# ESC.net
KiCad netlist of a schematic drawn in EAGLE
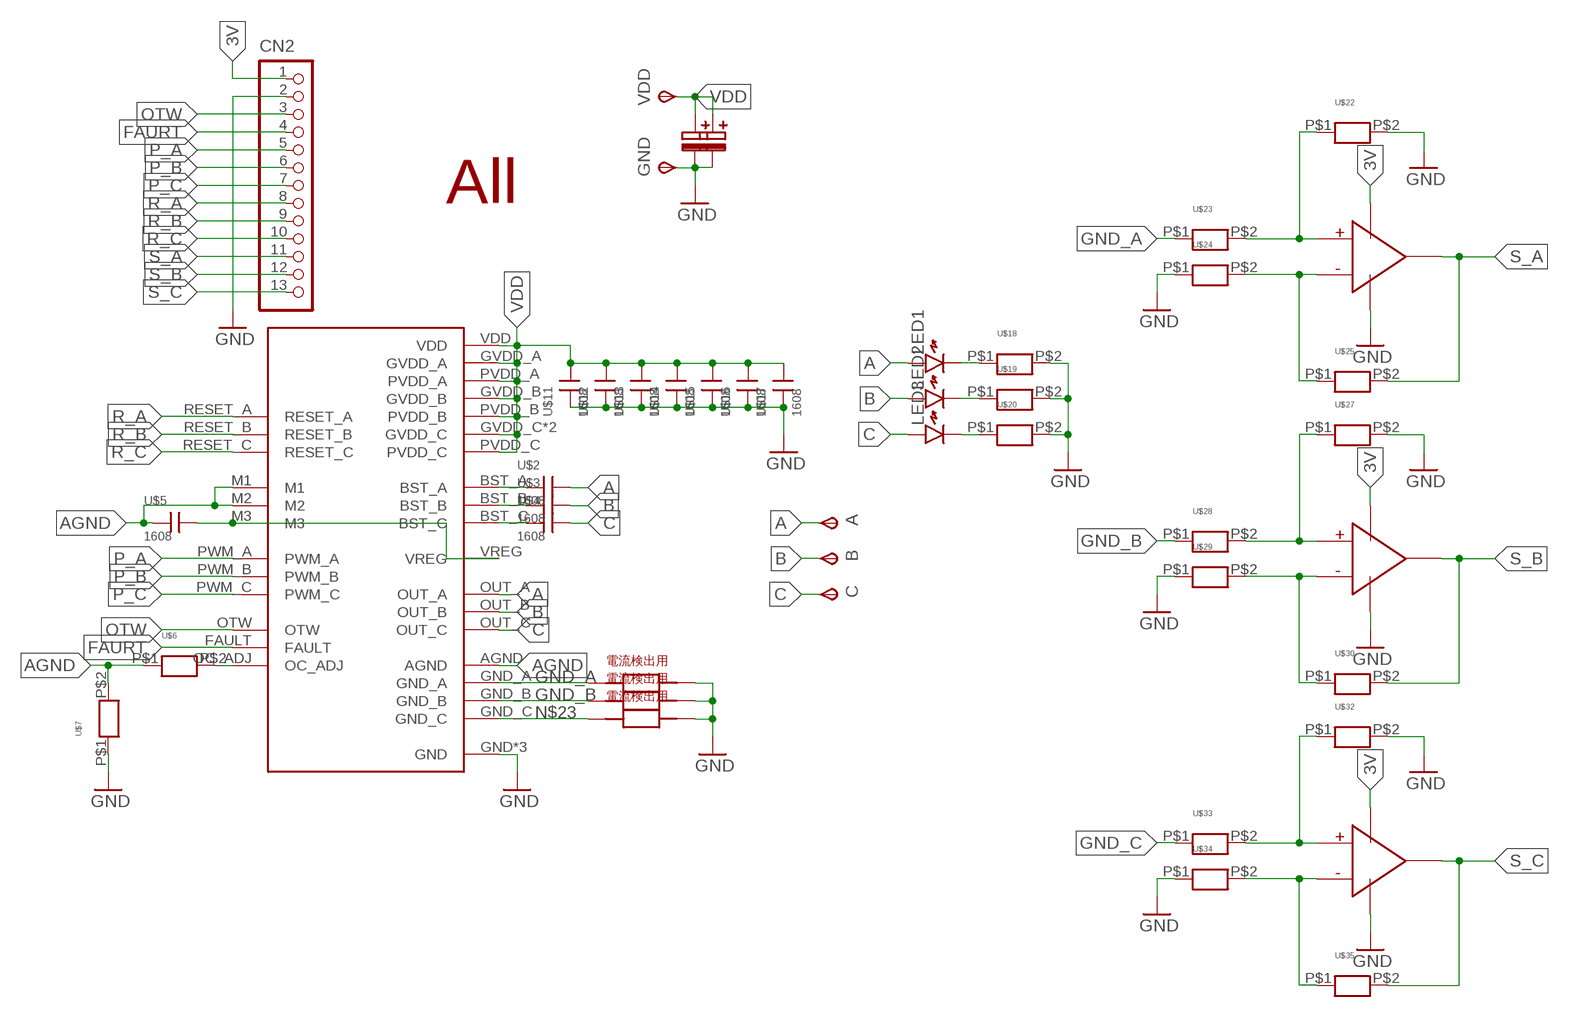
[diagram p0: schematic, sheet 1]

(export (version "E")
  (design (tool "Eeschema 10.0.6"))
  (components
    (comp (ref "A")
      (value "TPSPAD1-20")
      (footprint "eagle-import:P1-20")
      (libsource (lib "eagle-import") (part "TPSPAD1-20"))
    )
    (comp (ref "B")
      (value "TPSPAD1-20")
      (footprint "eagle-import:P1-20")
      (libsource (lib "eagle-import") (part "TPSPAD1-20"))
    )
    (comp (ref "C")
      (value "TPSPAD1-20")
      (footprint "eagle-import:P1-20")
      (libsource (lib "eagle-import") (part "TPSPAD1-20"))
    )
    (comp (ref "CN2")
      (value "B13B-XH-A")
      (footprint "eagle-import:B13B-XH-A")
      (libsource (lib "eagle-import") (part "B13B-XH-A"))
    )
    (comp (ref "GND")
      (value "TPSPAD1-20")
      (footprint "eagle-import:P1-20")
      (libsource (lib "eagle-import") (part "TPSPAD1-20"))
    )
    (comp (ref "LED1")
      (value "LED1608")
      (footprint "eagle-import:LED1608")
      (libsource (lib "eagle-import") (part "LED1608"))
    )
    (comp (ref "LED2")
      (value "LED1608")
      (footprint "eagle-import:LED1608")
      (libsource (lib "eagle-import") (part "LED1608"))
    )
    (comp (ref "LED3")
      (value "LED1608")
      (footprint "eagle-import:LED1608")
      (libsource (lib "eagle-import") (part "LED1608"))
    )
    (comp (ref "U$1")
      (value "DRV8332")
      (footprint "eagle-import:DRV8332")
      (libsource (lib "eagle-import") (part "DRV8332"))
    )
    (comp (ref "U$2")
      (value "1608")
      (footprint "eagle-import:CON")
      (libsource (lib "eagle-import") (part "1608"))
    )
    (comp (ref "U$3")
      (value "1608")
      (footprint "eagle-import:CON")
      (libsource (lib "eagle-import") (part "1608"))
    )
    (comp (ref "U$4")
      (value "1608")
      (footprint "eagle-import:CON")
      (libsource (lib "eagle-import") (part "1608"))
    )
    (comp (ref "U$5")
      (value "1608")
      (footprint "eagle-import:CON")
      (libsource (lib "eagle-import") (part "1608"))
    )
    (comp (ref "U$6") (value "R") (footprint "eagle-import:1608") (libsource (lib "eagle-import") (part "R")))
    (comp (ref "U$7") (value "R") (footprint "eagle-import:1608") (libsource (lib "eagle-import") (part "R")))
    (comp (ref "U$8")
      (value "R0.1")
      (footprint "eagle-import:R0.1")
      (libsource (lib "eagle-import") (part "R0.1"))
    )
    (comp (ref "U$9")
      (value "R0.1")
      (footprint "eagle-import:R0.1")
      (libsource (lib "eagle-import") (part "R0.1"))
    )
    (comp (ref "U$10")
      (value "R0.1")
      (footprint "eagle-import:R0.1")
      (libsource (lib "eagle-import") (part "R0.1"))
    )
    (comp (ref "U$11")
      (value "1608")
      (footprint "eagle-import:CON")
      (libsource (lib "eagle-import") (part "1608"))
    )
    (comp (ref "U$12")
      (value "1608")
      (footprint "eagle-import:CON")
      (libsource (lib "eagle-import") (part "1608"))
    )
    (comp (ref "U$13")
      (value "1608")
      (footprint "eagle-import:CON")
      (libsource (lib "eagle-import") (part "1608"))
    )
    (comp (ref "U$14")
      (value "1608")
      (footprint "eagle-import:CON")
      (libsource (lib "eagle-import") (part "1608"))
    )
    (comp (ref "U$15")
      (value "1608")
      (footprint "eagle-import:CON")
      (libsource (lib "eagle-import") (part "1608"))
    )
    (comp (ref "U$16")
      (value "1608")
      (footprint "eagle-import:CON")
      (libsource (lib "eagle-import") (part "1608"))
    )
    (comp (ref "U$17")
      (value "1608")
      (footprint "eagle-import:CON")
      (libsource (lib "eagle-import") (part "1608"))
    )
    (comp (ref "U$18")
      (value "R")
      (footprint "eagle-import:1608")
      (libsource (lib "eagle-import") (part "R"))
    )
    (comp (ref "U$19")
      (value "R")
      (footprint "eagle-import:1608")
      (libsource (lib "eagle-import") (part "R"))
    )
    (comp (ref "U$20")
      (value "R")
      (footprint "eagle-import:1608")
      (libsource (lib "eagle-import") (part "R"))
    )
    (comp (ref "U$21")
      (value "77701")
      (footprint "eagle-import:77701")
      (libsource (lib "eagle-import") (part "77701"))
    )
    (comp (ref "U$22")
      (value "R")
      (footprint "eagle-import:1608")
      (libsource (lib "eagle-import") (part "R"))
    )
    (comp (ref "U$23")
      (value "R")
      (footprint "eagle-import:1608")
      (libsource (lib "eagle-import") (part "R"))
    )
    (comp (ref "U$24")
      (value "R")
      (footprint "eagle-import:1608")
      (libsource (lib "eagle-import") (part "R"))
    )
    (comp (ref "U$25")
      (value "R")
      (footprint "eagle-import:1608")
      (libsource (lib "eagle-import") (part "R"))
    )
    (comp (ref "U$26")
      (value "77701")
      (footprint "eagle-import:77701")
      (libsource (lib "eagle-import") (part "77701"))
    )
    (comp (ref "U$27")
      (value "R")
      (footprint "eagle-import:1608")
      (libsource (lib "eagle-import") (part "R"))
    )
    (comp (ref "U$28")
      (value "R")
      (footprint "eagle-import:1608")
      (libsource (lib "eagle-import") (part "R"))
    )
    (comp (ref "U$29")
      (value "R")
      (footprint "eagle-import:1608")
      (libsource (lib "eagle-import") (part "R"))
    )
    (comp (ref "U$30")
      (value "R")
      (footprint "eagle-import:1608")
      (libsource (lib "eagle-import") (part "R"))
    )
    (comp (ref "U$31")
      (value "77701")
      (footprint "eagle-import:77701")
      (libsource (lib "eagle-import") (part "77701"))
    )
    (comp (ref "U$32")
      (value "R")
      (footprint "eagle-import:1608")
      (libsource (lib "eagle-import") (part "R"))
    )
    (comp (ref "U$33")
      (value "R")
      (footprint "eagle-import:1608")
      (libsource (lib "eagle-import") (part "R"))
    )
    (comp (ref "U$34")
      (value "R")
      (footprint "eagle-import:1608")
      (libsource (lib "eagle-import") (part "R"))
    )
    (comp (ref "U$35")
      (value "R")
      (footprint "eagle-import:1608")
      (libsource (lib "eagle-import") (part "R"))
    )
    (comp (ref "U$36")
      (value "25V100")
      (footprint "eagle-import:25V100")
      (libsource (lib "eagle-import") (part "25V100"))
    )
    (comp (ref "U$37")
      (value "25V100")
      (footprint "eagle-import:25V100")
      (libsource (lib "eagle-import") (part "25V100"))
    )
    (comp (ref "U$38")
      (value "ALL")
      (footprint "eagle-import:ALL")
      (libsource (lib "eagle-import") (part "ALL"))
    )
    (comp (ref "VDD")
      (value "TPSPAD1-20")
      (footprint "eagle-import:P1-20")
      (libsource (lib "eagle-import") (part "TPSPAD1-20"))
    )
  )
  (nets
    (net (code "1") (name "/N$23") (class "Default")
      (node (ref "U$1") (pin "GND_C") (pinfunction "GND_C_GND_C") (pintype "bidirectional"))
      (node (ref "U$10") (pin "P$1") (pinfunction "P$1_P$1") (pintype "bidirectional"))
    )
    (net (code "2") (name "3V") (class "Default")
      (node (ref "CN2") (pin "1") (pinfunction "1_1") (pintype "passive"))
      (node (ref "U$21") (pin "VIN") (pinfunction "VIN_VIN") (pintype "bidirectional"))
      (node (ref "U$26") (pin "VIN") (pinfunction "VIN_VIN") (pintype "bidirectional"))
      (node (ref "U$31") (pin "VIN") (pinfunction "VIN_VIN") (pintype "bidirectional"))
    )
    (net (code "3") (name "A") (class "Default")
      (node (ref "A") (pin "TP") (pinfunction "PP_TP") (pintype "input"))
      (node (ref "LED1") (pin "A") (pinfunction "A_A") (pintype "passive"))
      (node (ref "U$1") (pin "OUT_A") (pinfunction "OUT_A_OUT_A") (pintype "bidirectional"))
      (node (ref "U$2") (pin "P$1") (pinfunction "1_P$1") (pintype "bidirectional"))
    )
    (net (code "4") (name "AGND") (class "Default")
      (node (ref "U$1") (pin "AGND") (pinfunction "AGND_AGND") (pintype "bidirectional"))
      (node (ref "U$1") (pin "M1") (pinfunction "M1_M1") (pintype "bidirectional"))
      (node (ref "U$1") (pin "M2") (pinfunction "M2_M2") (pintype "bidirectional"))
      (node (ref "U$5") (pin "P$2") (pinfunction "2_P$2") (pintype "bidirectional"))
      (node (ref "U$6") (pin "P$1") (pinfunction "P$1_P$1") (pintype "bidirectional"))
      (node (ref "U$7") (pin "P$2") (pinfunction "P$2_P$2") (pintype "bidirectional"))
    )
    (net (code "5") (name "B") (class "Default")
      (node (ref "B") (pin "TP") (pinfunction "PP_TP") (pintype "input"))
      (node (ref "LED2") (pin "A") (pinfunction "A_A") (pintype "passive"))
      (node (ref "U$1") (pin "OUT_B") (pinfunction "OUT_B_OUT_B") (pintype "bidirectional"))
      (node (ref "U$3") (pin "P$1") (pinfunction "1_P$1") (pintype "bidirectional"))
    )
    (net (code "6") (name "C") (class "Default")
      (node (ref "C") (pin "TP") (pinfunction "PP_TP") (pintype "input"))
      (node (ref "LED3") (pin "A") (pinfunction "A_A") (pintype "passive"))
      (node (ref "U$1") (pin "OUT_C") (pinfunction "OUT_C_OUT_C") (pintype "bidirectional"))
      (node (ref "U$4") (pin "P$1") (pinfunction "1_P$1") (pintype "bidirectional"))
    )
    (net (code "7") (name "FAURT") (class "Default")
      (node (ref "CN2") (pin "4") (pinfunction "4_4") (pintype "passive"))
      (node (ref "U$1") (pin "FAULT") (pinfunction "FAULT_FAULT") (pintype "bidirectional"))
    )
    (net (code "8") (name "GND") (class "Default")
      (node (ref "CN2") (pin "2") (pinfunction "2_2") (pintype "passive"))
      (node (ref "GND") (pin "TP") (pinfunction "PP_TP") (pintype "input"))
      (node (ref "U$1") (pin "GND") (pinfunction "GND_GND") (pintype "bidirectional"))
      (node (ref "U$1") (pin "GND1") (pinfunction "GND_GND1") (pintype "bidirectional"))
      (node (ref "U$1") (pin "GND2") (pinfunction "GND_GND2") (pintype "bidirectional"))
      (node (ref "U$10") (pin "P$2") (pinfunction "P$2_P$2") (pintype "bidirectional"))
      (node (ref "U$11") (pin "P$2") (pinfunction "2_P$2") (pintype "bidirectional"))
      (node (ref "U$12") (pin "P$2") (pinfunction "2_P$2") (pintype "bidirectional"))
      (node (ref "U$13") (pin "P$2") (pinfunction "2_P$2") (pintype "bidirectional"))
      (node (ref "U$14") (pin "P$2") (pinfunction "2_P$2") (pintype "bidirectional"))
      (node (ref "U$15") (pin "P$2") (pinfunction "2_P$2") (pintype "bidirectional"))
      (node (ref "U$16") (pin "P$2") (pinfunction "2_P$2") (pintype "bidirectional"))
      (node (ref "U$17") (pin "P$2") (pinfunction "2_P$2") (pintype "bidirectional"))
      (node (ref "U$18") (pin "P$2") (pinfunction "P$2_P$2") (pintype "bidirectional"))
      (node (ref "U$19") (pin "P$2") (pinfunction "P$2_P$2") (pintype "bidirectional"))
      (node (ref "U$20") (pin "P$2") (pinfunction "P$2_P$2") (pintype "bidirectional"))
      (node (ref "U$21") (pin "VOUT") (pinfunction "VOUT_VOUT") (pintype "bidirectional"))
      (node (ref "U$22") (pin "P$2") (pinfunction "P$2_P$2") (pintype "bidirectional"))
      (node (ref "U$24") (pin "P$1") (pinfunction "P$1_P$1") (pintype "bidirectional"))
      (node (ref "U$26") (pin "VOUT") (pinfunction "VOUT_VOUT") (pintype "bidirectional"))
      (node (ref "U$27") (pin "P$2") (pinfunction "P$2_P$2") (pintype "bidirectional"))
      (node (ref "U$29") (pin "P$1") (pinfunction "P$1_P$1") (pintype "bidirectional"))
      (node (ref "U$31") (pin "VOUT") (pinfunction "VOUT_VOUT") (pintype "bidirectional"))
      (node (ref "U$32") (pin "P$2") (pinfunction "P$2_P$2") (pintype "bidirectional"))
      (node (ref "U$34") (pin "P$1") (pinfunction "P$1_P$1") (pintype "bidirectional"))
      (node (ref "U$36") (pin "P$2") (pinfunction "P$2_P$2") (pintype "bidirectional"))
      (node (ref "U$37") (pin "P$2") (pinfunction "P$2_P$2") (pintype "bidirectional"))
      (node (ref "U$7") (pin "P$1") (pinfunction "P$1_P$1") (pintype "bidirectional"))
      (node (ref "U$8") (pin "P$2") (pinfunction "P$2_P$2") (pintype "bidirectional"))
      (node (ref "U$9") (pin "P$2") (pinfunction "P$2_P$2") (pintype "bidirectional"))
    )
    (net (code "9") (name "GND_A") (class "Default")
      (node (ref "U$1") (pin "GND_A") (pinfunction "GND_A_GND_A") (pintype "bidirectional"))
      (node (ref "U$23") (pin "P$1") (pinfunction "P$1_P$1") (pintype "bidirectional"))
      (node (ref "U$8") (pin "P$1") (pinfunction "P$1_P$1") (pintype "bidirectional"))
    )
    (net (code "10") (name "GND_B") (class "Default")
      (node (ref "U$1") (pin "GND_B") (pinfunction "GND_B_GND_B") (pintype "bidirectional"))
      (node (ref "U$28") (pin "P$1") (pinfunction "P$1_P$1") (pintype "bidirectional"))
      (node (ref "U$9") (pin "P$1") (pinfunction "P$1_P$1") (pintype "bidirectional"))
    )
    (net (code "11") (name "GND_C") (class "Default")
      (node (ref "U$33") (pin "P$1") (pinfunction "P$1_P$1") (pintype "bidirectional"))
    )
    (net (code "12") (name "Net-(LED1-PadK)") (class "Default")
      (node (ref "LED1") (pin "K") (pinfunction "K_K") (pintype "passive"))
      (node (ref "U$18") (pin "P$1") (pinfunction "P$1_P$1") (pintype "bidirectional"))
    )
    (net (code "13") (name "Net-(LED2-PadK)") (class "Default")
      (node (ref "LED2") (pin "K") (pinfunction "K_K") (pintype "passive"))
      (node (ref "U$19") (pin "P$1") (pinfunction "P$1_P$1") (pintype "bidirectional"))
    )
    (net (code "14") (name "Net-(LED3-PadK)") (class "Default")
      (node (ref "LED3") (pin "K") (pinfunction "K_K") (pintype "passive"))
      (node (ref "U$20") (pin "P$1") (pinfunction "P$1_P$1") (pintype "bidirectional"))
    )
    (net (code "15") (name "Net-(U$1-PadOC_ADJ)") (class "Default")
      (node (ref "U$1") (pin "OC_ADJ") (pinfunction "OC_ADJ_OC_ADJ") (pintype "bidirectional"))
      (node (ref "U$6") (pin "P$2") (pinfunction "P$2_P$2") (pintype "bidirectional"))
    )
    (net (code "16") (name "Net-(U$2-2)") (class "Default")
      (node (ref "U$1") (pin "BST_A") (pinfunction "BST_A_BST_A") (pintype "bidirectional"))
      (node (ref "U$2") (pin "P$2") (pinfunction "2_P$2") (pintype "bidirectional"))
    )
    (net (code "17") (name "Net-(U$3-2)") (class "Default")
      (node (ref "U$1") (pin "BST_B") (pinfunction "BST_B_BST_B") (pintype "bidirectional"))
      (node (ref "U$3") (pin "P$2") (pinfunction "2_P$2") (pintype "bidirectional"))
    )
    (net (code "18") (name "Net-(U$4-2)") (class "Default")
      (node (ref "U$1") (pin "BST_C") (pinfunction "BST_C_BST_C") (pintype "bidirectional"))
      (node (ref "U$4") (pin "P$2") (pinfunction "2_P$2") (pintype "bidirectional"))
    )
    (net (code "19") (name "Net-(U$5-1)") (class "Default")
      (node (ref "U$1") (pin "M3") (pinfunction "M3_M3") (pintype "bidirectional"))
      (node (ref "U$1") (pin "VREG") (pinfunction "VREG_VREG") (pintype "bidirectional"))
      (node (ref "U$5") (pin "P$1") (pinfunction "1_P$1") (pintype "bidirectional"))
    )
    (net (code "20") (name "Net-(U$21-Pad+)") (class "Default")
      (node (ref "U$21") (pin "+") (pinfunction "+_+") (pintype "bidirectional"))
      (node (ref "U$22") (pin "P$1") (pinfunction "P$1_P$1") (pintype "bidirectional"))
      (node (ref "U$23") (pin "P$2") (pinfunction "P$2_P$2") (pintype "bidirectional"))
    )
    (net (code "21") (name "Net-(U$21-Pad-)") (class "Default")
      (node (ref "U$21") (pin "-") (pinfunction "-_-") (pintype "bidirectional"))
      (node (ref "U$24") (pin "P$2") (pinfunction "P$2_P$2") (pintype "bidirectional"))
      (node (ref "U$25") (pin "P$1") (pinfunction "P$1_P$1") (pintype "bidirectional"))
    )
    (net (code "22") (name "Net-(U$26-Pad+)") (class "Default")
      (node (ref "U$26") (pin "+") (pinfunction "+_+") (pintype "bidirectional"))
      (node (ref "U$27") (pin "P$1") (pinfunction "P$1_P$1") (pintype "bidirectional"))
      (node (ref "U$28") (pin "P$2") (pinfunction "P$2_P$2") (pintype "bidirectional"))
    )
    (net (code "23") (name "Net-(U$26-Pad-)") (class "Default")
      (node (ref "U$26") (pin "-") (pinfunction "-_-") (pintype "bidirectional"))
      (node (ref "U$29") (pin "P$2") (pinfunction "P$2_P$2") (pintype "bidirectional"))
      (node (ref "U$30") (pin "P$1") (pinfunction "P$1_P$1") (pintype "bidirectional"))
    )
    (net (code "24") (name "Net-(U$31-Pad+)") (class "Default")
      (node (ref "U$31") (pin "+") (pinfunction "+_+") (pintype "bidirectional"))
      (node (ref "U$32") (pin "P$1") (pinfunction "P$1_P$1") (pintype "bidirectional"))
      (node (ref "U$33") (pin "P$2") (pinfunction "P$2_P$2") (pintype "bidirectional"))
    )
    (net (code "25") (name "Net-(U$31-Pad-)") (class "Default")
      (node (ref "U$31") (pin "-") (pinfunction "-_-") (pintype "bidirectional"))
      (node (ref "U$34") (pin "P$2") (pinfunction "P$2_P$2") (pintype "bidirectional"))
      (node (ref "U$35") (pin "P$1") (pinfunction "P$1_P$1") (pintype "bidirectional"))
    )
    (net (code "26") (name "OTW") (class "Default")
      (node (ref "CN2") (pin "3") (pinfunction "3_3") (pintype "passive"))
      (node (ref "U$1") (pin "OTW") (pinfunction "OTW_OTW") (pintype "bidirectional"))
    )
    (net (code "27") (name "P_A") (class "Default")
      (node (ref "CN2") (pin "5") (pinfunction "5_5") (pintype "passive"))
      (node (ref "U$1") (pin "PWM_A") (pinfunction "PWM_A_PWM_A") (pintype "bidirectional"))
    )
    (net (code "28") (name "P_B") (class "Default")
      (node (ref "CN2") (pin "6") (pinfunction "6_6") (pintype "passive"))
      (node (ref "U$1") (pin "PWM_B") (pinfunction "PWM_B_PWM_B") (pintype "bidirectional"))
    )
    (net (code "29") (name "P_C") (class "Default")
      (node (ref "CN2") (pin "7") (pinfunction "7_7") (pintype "passive"))
      (node (ref "U$1") (pin "PWM_C") (pinfunction "PWM_C_PWM_C") (pintype "bidirectional"))
    )
    (net (code "30") (name "R_A") (class "Default")
      (node (ref "CN2") (pin "8") (pinfunction "8_8") (pintype "passive"))
      (node (ref "U$1") (pin "RESET_A") (pinfunction "RESET_A_RESET_A") (pintype "bidirectional"))
    )
    (net (code "31") (name "R_B") (class "Default")
      (node (ref "CN2") (pin "9") (pinfunction "9_9") (pintype "passive"))
      (node (ref "U$1") (pin "RESET_B") (pinfunction "RESET_B_RESET_B") (pintype "bidirectional"))
    )
    (net (code "32") (name "R_C") (class "Default")
      (node (ref "CN2") (pin "10") (pinfunction "10_10") (pintype "passive"))
      (node (ref "U$1") (pin "RESET_C") (pinfunction "RESET_C_RESET_C") (pintype "bidirectional"))
    )
    (net (code "33") (name "S_A") (class "Default")
      (node (ref "CN2") (pin "11") (pinfunction "11_11") (pintype "passive"))
      (node (ref "U$21") (pin "O") (pinfunction "O_O") (pintype "bidirectional"))
      (node (ref "U$25") (pin "P$2") (pinfunction "P$2_P$2") (pintype "bidirectional"))
    )
    (net (code "34") (name "S_B") (class "Default")
      (node (ref "CN2") (pin "12") (pinfunction "12_12") (pintype "passive"))
      (node (ref "U$26") (pin "O") (pinfunction "O_O") (pintype "bidirectional"))
      (node (ref "U$30") (pin "P$2") (pinfunction "P$2_P$2") (pintype "bidirectional"))
    )
    (net (code "35") (name "S_C") (class "Default")
      (node (ref "CN2") (pin "13") (pinfunction "13_13") (pintype "passive"))
      (node (ref "U$31") (pin "O") (pinfunction "O_O") (pintype "bidirectional"))
      (node (ref "U$35") (pin "P$2") (pinfunction "P$2_P$2") (pintype "bidirectional"))
    )
    (net (code "36") (name "VDD") (class "Default")
      (node (ref "U$1") (pin "GVDD_A") (pinfunction "GVDD_A_GVDD_A") (pintype "bidirectional"))
      (node (ref "U$1") (pin "GVDD_B") (pinfunction "GVDD_B_GVDD_B") (pintype "bidirectional"))
      (node (ref "U$1") (pin "GVDD_C") (pinfunction "GVDD_C_GVDD_C") (pintype "bidirectional"))
      (node (ref "U$1") (pin "GVDD_C2") (pinfunction "GVDD_C_GVDD_C2") (pintype "bidirectional"))
      (node (ref "U$1") (pin "PVDD_A") (pinfunction "PVDD_A_PVDD_A") (pintype "bidirectional"))
      (node (ref "U$1") (pin "PVDD_B") (pinfunction "PVDD_B_PVDD_B") (pintype "bidirectional"))
      (node (ref "U$1") (pin "PVDD_C") (pinfunction "PVDD_C_PVDD_C") (pintype "bidirectional"))
      (node (ref "U$1") (pin "VDD") (pinfunction "VDD_VDD") (pintype "bidirectional"))
      (node (ref "U$11") (pin "P$1") (pinfunction "1_P$1") (pintype "bidirectional"))
      (node (ref "U$12") (pin "P$1") (pinfunction "1_P$1") (pintype "bidirectional"))
      (node (ref "U$13") (pin "P$1") (pinfunction "1_P$1") (pintype "bidirectional"))
      (node (ref "U$14") (pin "P$1") (pinfunction "1_P$1") (pintype "bidirectional"))
      (node (ref "U$15") (pin "P$1") (pinfunction "1_P$1") (pintype "bidirectional"))
      (node (ref "U$16") (pin "P$1") (pinfunction "1_P$1") (pintype "bidirectional"))
      (node (ref "U$17") (pin "P$1") (pinfunction "1_P$1") (pintype "bidirectional"))
      (node (ref "U$36") (pin "P$1") (pinfunction "P$1_P$1") (pintype "bidirectional"))
      (node (ref "U$37") (pin "P$1") (pinfunction "P$1_P$1") (pintype "bidirectional"))
      (node (ref "VDD") (pin "TP") (pinfunction "PP_TP") (pintype "input"))
    )
  )
)
